# UNO_florist_automata_V1_0.net
KiCad netlist of a schematic drawn in EAGLE
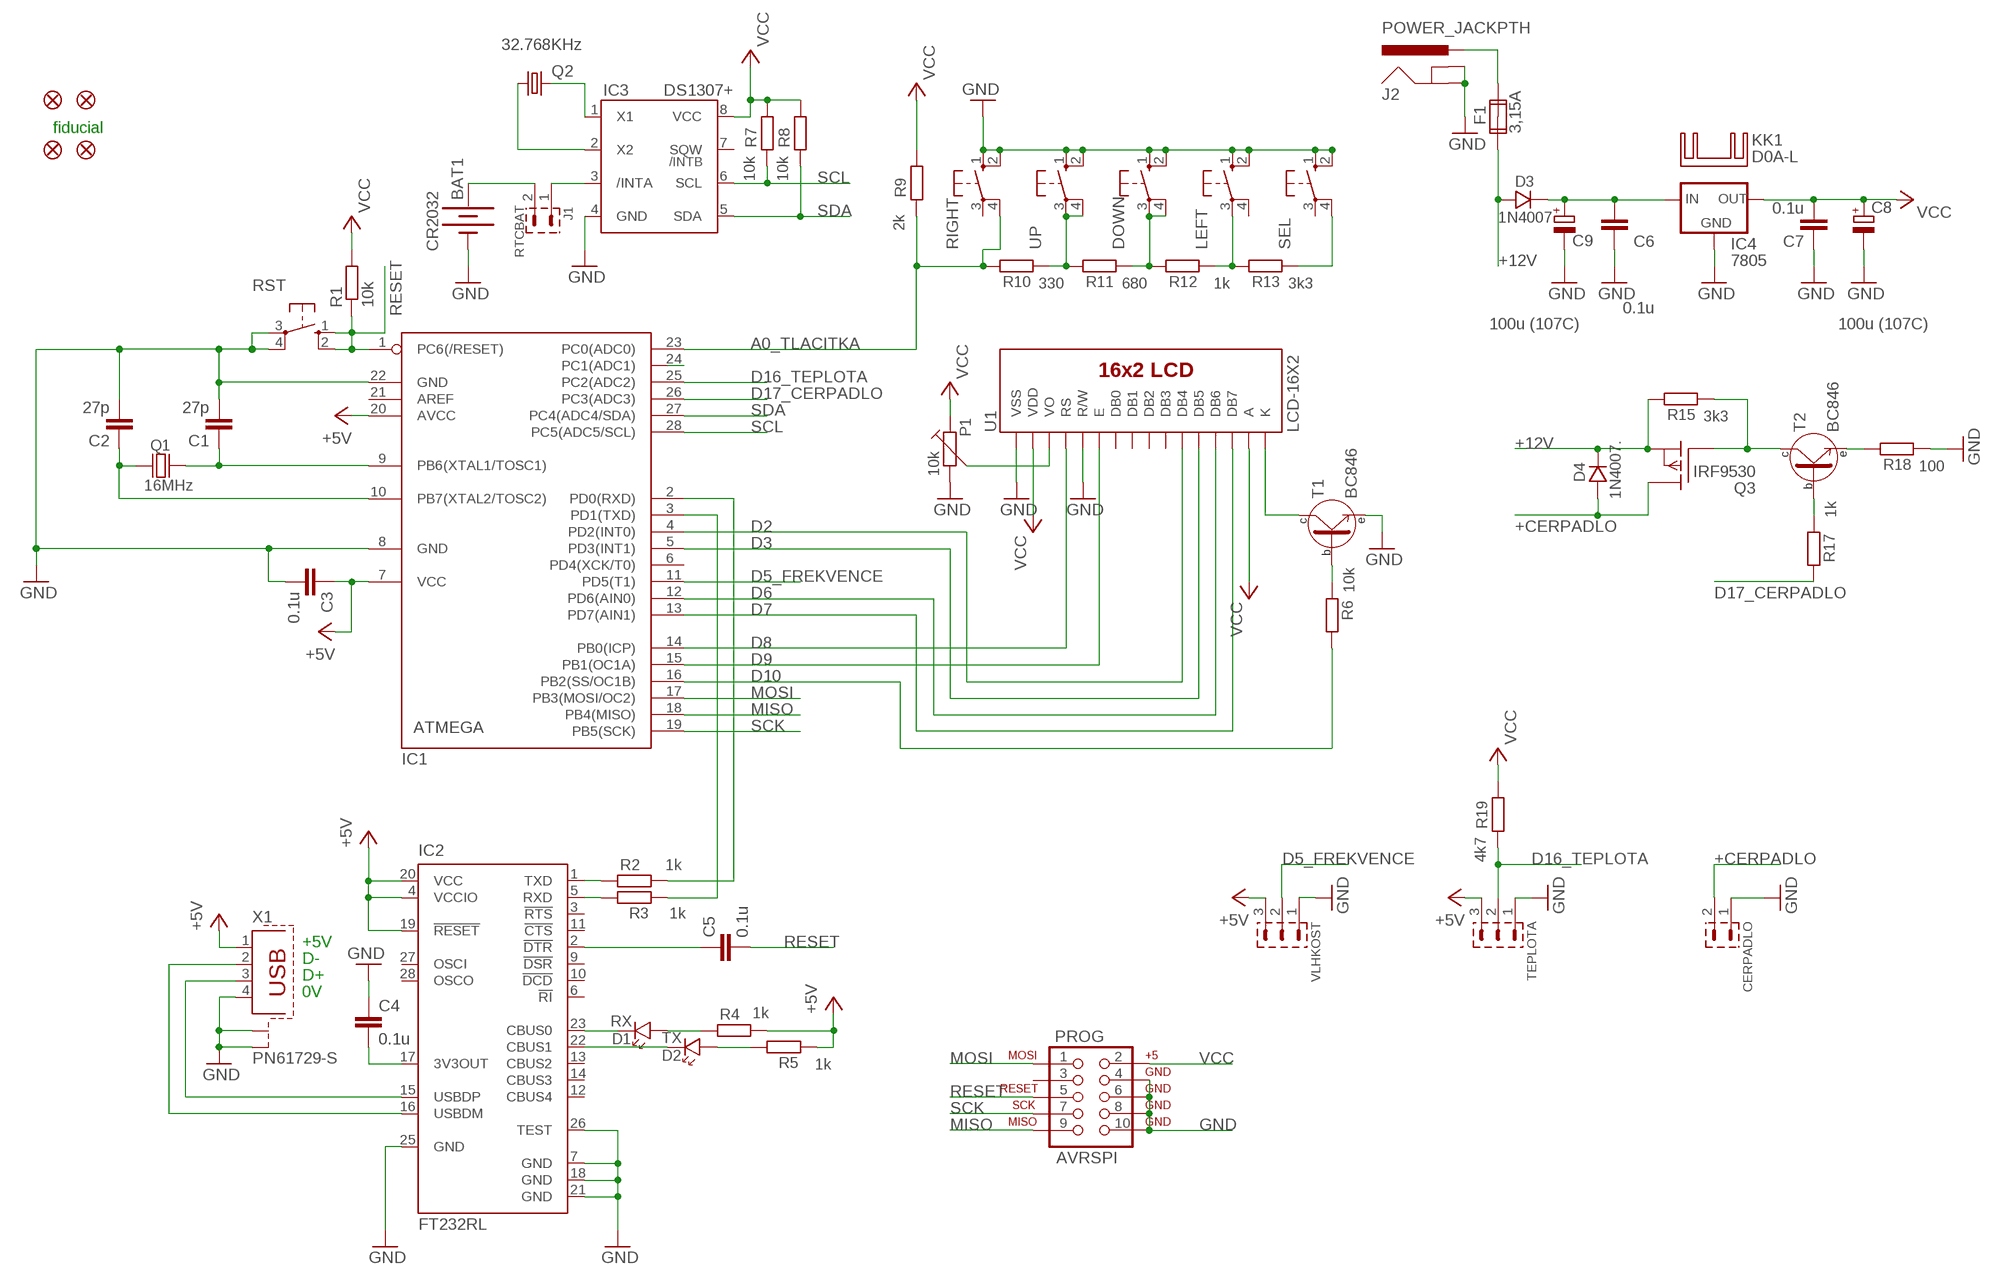
[diagram p0: schematic, sheet 1]

(export (version "E")
  (design (tool "Eeschema 10.0.6"))
  (components
    (comp (ref "BAT1")
      (value "CR2032")
      (footprint "eagle-import:BATTCOM_20MM_PTH")
      (libsource (lib "eagle-import") (part "BATTERY20PTH"))
    )
    (comp (ref "C1")
      (value "27p")
      (footprint "eagle-import:C1206")
      (libsource (lib "eagle-import") (part "C-EUC1206"))
    )
    (comp (ref "C2")
      (value "27p")
      (footprint "eagle-import:C1206")
      (libsource (lib "eagle-import") (part "C-EUC1206"))
    )
    (comp (ref "C3")
      (value "0.1u")
      (footprint "eagle-import:C1206")
      (libsource (lib "eagle-import") (part "C-EUC1206"))
    )
    (comp (ref "C4")
      (value "0.1u")
      (footprint "eagle-import:C1206")
      (libsource (lib "eagle-import") (part "C-EUC1206"))
    )
    (comp (ref "C5")
      (value "0.1u")
      (footprint "eagle-import:C1206")
      (libsource (lib "eagle-import") (part "C-EUC1206"))
    )
    (comp (ref "C6")
      (value "0.1u")
      (footprint "eagle-import:C1206")
      (libsource (lib "eagle-import") (part "C-EUC1206"))
    )
    (comp (ref "C7")
      (value "0.1u")
      (footprint "eagle-import:C1206")
      (libsource (lib "eagle-import") (part "C-EUC1206"))
    )
    (comp (ref "C8")
      (value "100u (107C)")
      (footprint "eagle-import:C_6032-28W")
      (libsource (lib "eagle-import") (part "CPOL-EUC/6032-28W"))
    )
    (comp (ref "C9")
      (value "100u (107C)")
      (footprint "eagle-import:C_6032-28W")
      (libsource (lib "eagle-import") (part "CPOL-EUC/6032-28W"))
    )
    (comp (ref "CERPADLO")
      (value "PSH02-02P")
      (footprint "eagle-import:PSH02-02P")
      (libsource (lib "eagle-import") (part "PSH02-02P"))
    )
    (comp (ref "D1")
      (value "RX")
      (footprint "eagle-import:P1206")
      (libsource (lib "eagle-import") (part "LED_1206"))
    )
    (comp (ref "D2")
      (value "TX")
      (footprint "eagle-import:P1206")
      (libsource (lib "eagle-import") (part "LED_1206"))
    )
    (comp (ref "D3")
      (value "1N4007.")
      (footprint "eagle-import:SM-1")
      (libsource (lib "eagle-import") (part "1N4007."))
    )
    (comp (ref "D4")
      (value "1N4007.")
      (footprint "eagle-import:SM-1")
      (libsource (lib "eagle-import") (part "1N4007."))
    )
    (comp (ref "DOWN")
      (value "10-XX")
      (footprint "eagle-import:B3F-10XX")
      (libsource (lib "eagle-import") (part "10-XX"))
    )
    (comp (ref "F1")
      (value "3,15A")
      (footprint "eagle-import:FUSE1")
      (libsource (lib "eagle-import") (part "FUSE2P"))
    )
    (comp (ref "FID1")
      (value "FIDUCIAL1.5X3")
      (footprint "eagle-import:FIDUCIAL-1.5X3")
      (libsource (lib "eagle-import") (part "FIDUCIAL1.5X3"))
    )
    (comp (ref "FID2")
      (value "FIDUCIAL1.5X3")
      (footprint "eagle-import:FIDUCIAL-1.5X3")
      (libsource (lib "eagle-import") (part "FIDUCIAL1.5X3"))
    )
    (comp (ref "FID3")
      (value "FIDUCIAL1.5X3")
      (footprint "eagle-import:FIDUCIAL-1.5X3")
      (libsource (lib "eagle-import") (part "FIDUCIAL1.5X3"))
    )
    (comp (ref "FID4")
      (value "FIDUCIAL1.5X3")
      (footprint "eagle-import:FIDUCIAL-1.5X3")
      (libsource (lib "eagle-import") (part "FIDUCIAL1.5X3"))
    )
    (comp (ref "IC1")
      (value "ATMEGA")
      (footprint "eagle-import:DIL28-3")
      (libsource (lib "eagle-import") (part "MEGA8-P"))
    )
    (comp (ref "IC2")
      (value "FT232RL")
      (footprint "eagle-import:SSOP28")
      (libsource (lib "eagle-import") (part "FT232RL"))
    )
    (comp (ref "IC3")
      (value "DS1307+")
      (footprint "eagle-import:SO08")
      (libsource (lib "eagle-import") (part "DS1337S+"))
    )
    (comp (ref "IC4")
      (value "7805")
      (footprint "eagle-import:78XXL")
      (libsource (lib "eagle-import") (part "78XXL"))
    )
    (comp (ref "J1")
      (value "RTCBAT")
      (footprint "eagle-import:S1G2_JUM")
      (libsource (lib "eagle-import") (part "S1G2_JUMP"))
    )
    (comp (ref "J2")
      (value "POWER_JACKPTH")
      (footprint "eagle-import:POWER_JACK_PTH")
      (libsource (lib "eagle-import") (part "POWER_JACKPTH"))
    )
    (comp (ref "KK1")
      (value "D0A-L")
      (footprint "eagle-import:D02A-L")
      (libsource (lib "eagle-import") (part "D0A-L"))
    )
    (comp (ref "LEFT")
      (value "10-XX")
      (footprint "eagle-import:B3F-10XX")
      (libsource (lib "eagle-import") (part "10-XX"))
    )
    (comp (ref "P1")
      (value "10k")
      (footprint "eagle-import:PT10V")
      (libsource (lib "eagle-import") (part "TRIMRPT10V"))
    )
    (comp (ref "PROG")
      (value "AVRSPI")
      (footprint "eagle-import:2X5-SHROUDED_LOCK")
      (libsource (lib "eagle-import") (part "AVR_SPI_PROG2LOCK"))
    )
    (comp (ref "Q1")
      (value "16MHz")
      (footprint "eagle-import:HC-49U")
      (libsource (lib "eagle-import") (part "Q_HC-49U"))
    )
    (comp (ref "Q2")
      (value "32.768KHz")
      (footprint "eagle-import:TC38H")
      (libsource (lib "eagle-import") (part "CRYSTALTC38H"))
    )
    (comp (ref "Q3")
      (value "IRF9530")
      (footprint "eagle-import:TO220")
      (libsource (lib "eagle-import") (part "IRF9530"))
    )
    (comp (ref "R1")
      (value "10k")
      (footprint "eagle-import:M1206")
      (libsource (lib "eagle-import") (part "R-EU_M1206"))
    )
    (comp (ref "R2")
      (value "1k")
      (footprint "eagle-import:M1206")
      (libsource (lib "eagle-import") (part "R-EU_M1206"))
    )
    (comp (ref "R3")
      (value "1k")
      (footprint "eagle-import:M1206")
      (libsource (lib "eagle-import") (part "R-EU_M1206"))
    )
    (comp (ref "R4")
      (value "1k")
      (footprint "eagle-import:M1206")
      (libsource (lib "eagle-import") (part "R-EU_M1206"))
    )
    (comp (ref "R5")
      (value "1k")
      (footprint "eagle-import:M1206")
      (libsource (lib "eagle-import") (part "R-EU_M1206"))
    )
    (comp (ref "R6")
      (value "10k")
      (footprint "eagle-import:M1206")
      (libsource (lib "eagle-import") (part "R-EU_M1206"))
    )
    (comp (ref "R7")
      (value "10k")
      (footprint "eagle-import:M1206")
      (libsource (lib "eagle-import") (part "R-EU_M1206"))
    )
    (comp (ref "R8")
      (value "10k")
      (footprint "eagle-import:M1206")
      (libsource (lib "eagle-import") (part "R-EU_M1206"))
    )
    (comp (ref "R9")
      (value "2k")
      (footprint "eagle-import:M1206")
      (libsource (lib "eagle-import") (part "R-EU_M1206"))
    )
    (comp (ref "R10")
      (value "330")
      (footprint "eagle-import:M1206")
      (libsource (lib "eagle-import") (part "R-EU_M1206"))
    )
    (comp (ref "R11")
      (value "680")
      (footprint "eagle-import:M1206")
      (libsource (lib "eagle-import") (part "R-EU_M1206"))
    )
    (comp (ref "R12")
      (value "1k")
      (footprint "eagle-import:M1206")
      (libsource (lib "eagle-import") (part "R-EU_M1206"))
    )
    (comp (ref "R13")
      (value "3k3")
      (footprint "eagle-import:M1206")
      (libsource (lib "eagle-import") (part "R-EU_M1206"))
    )
    (comp (ref "R15")
      (value "3k3")
      (footprint "eagle-import:M1206")
      (libsource (lib "eagle-import") (part "R-EU_M1206"))
    )
    (comp (ref "R17")
      (value "1k")
      (footprint "eagle-import:M1206")
      (libsource (lib "eagle-import") (part "R-EU_M1206"))
    )
    (comp (ref "R18")
      (value "100")
      (footprint "eagle-import:M1206")
      (libsource (lib "eagle-import") (part "R-EU_M1206"))
    )
    (comp (ref "R19")
      (value "4k7")
      (footprint "eagle-import:M1206")
      (libsource (lib "eagle-import") (part "R-EU_M1206"))
    )
    (comp (ref "RIGHT")
      (value "10-XX")
      (footprint "eagle-import:B3F-10XX")
      (libsource (lib "eagle-import") (part "10-XX"))
    )
    (comp (ref "RST")
      (value "10-XX")
      (footprint "eagle-import:B3F-10XX")
      (libsource (lib "eagle-import") (part "10-XX"))
    )
    (comp (ref "SEL")
      (value "10-XX")
      (footprint "eagle-import:B3F-10XX")
      (libsource (lib "eagle-import") (part "10-XX"))
    )
    (comp (ref "T1")
      (value "BC846")
      (footprint "eagle-import:SOT-23")
      (libsource (lib "eagle-import") (part "BC846"))
    )
    (comp (ref "T2")
      (value "BC846")
      (footprint "eagle-import:SOT-23")
      (libsource (lib "eagle-import") (part "BC846"))
    )
    (comp (ref "TEPLOTA")
      (value "PSH02-03P")
      (footprint "eagle-import:PSH02-03P")
      (libsource (lib "eagle-import") (part "PSH02-03P"))
    )
    (comp (ref "U1")
      (value "LCD-16X2")
      (footprint "eagle-import:LCD-16X2_NOSILK")
      (libsource (lib "eagle-import") (part "LCD-16X2NOSILK"))
    )
    (comp (ref "UP")
      (value "10-XX")
      (footprint "eagle-import:B3F-10XX")
      (libsource (lib "eagle-import") (part "10-XX"))
    )
    (comp (ref "VLHKOST")
      (value "PSH02-03P")
      (footprint "eagle-import:PSH02-03P")
      (libsource (lib "eagle-import") (part "PSH02-03P"))
    )
    (comp (ref "X1")
      (value "PN61729-S")
      (footprint "eagle-import:PN61729-S")
      (libsource (lib "eagle-import") (part "PN61729-S"))
    )
  )
  (nets
    (net (code "1") (name "+5V") (class "Default")
      (node (ref "C3") (pin "1") (pinfunction "1_1") (pintype "passive"))
      (node (ref "C7") (pin "2") (pinfunction "2_2") (pintype "passive"))
      (node (ref "C8") (pin "+") (pinfunction "+_+") (pintype "passive"))
      (node (ref "IC1") (pin "20") (pinfunction "AVCC_20") (pintype "power_in"))
      (node (ref "IC1") (pin "7") (pinfunction "VCC_7") (pintype "power_in"))
      (node (ref "IC2") (pin "19") (pinfunction "~{RESET}_19") (pintype "input"))
      (node (ref "IC2") (pin "20") (pinfunction "VCC_20") (pintype "power_in"))
      (node (ref "IC2") (pin "4") (pinfunction "VCCIO_4") (pintype "power_in"))
      (node (ref "IC3") (pin "8") (pinfunction "VCC_8") (pintype "power_in"))
      (node (ref "IC4") (pin "OUT") (pinfunction "OUT_OUT") (pintype "passive"))
      (node (ref "P1") (pin "1") (pinfunction "1_1") (pintype "passive"))
      (node (ref "PROG") (pin "2") (pinfunction "2_2") (pintype "passive"))
      (node (ref "R1") (pin "2") (pinfunction "2_2") (pintype "passive"))
      (node (ref "R19") (pin "2") (pinfunction "2_2") (pintype "passive"))
      (node (ref "R4") (pin "2") (pinfunction "2_2") (pintype "passive"))
      (node (ref "R5") (pin "1") (pinfunction "1_1") (pintype "passive"))
      (node (ref "R7") (pin "2") (pinfunction "2_2") (pintype "passive"))
      (node (ref "R8") (pin "2") (pinfunction "2_2") (pintype "passive"))
      (node (ref "R9") (pin "2") (pinfunction "2_2") (pintype "passive"))
      (node (ref "TEPLOTA") (pin "3") (pinfunction "3_3") (pintype "passive"))
      (node (ref "U1") (pin "15") (pinfunction "A_15") (pintype "power_in"))
      (node (ref "U1") (pin "2") (pinfunction "VDD_2") (pintype "power_in"))
      (node (ref "VLHKOST") (pin "3") (pinfunction "3_3") (pintype "passive"))
      (node (ref "X1") (pin "1") (pinfunction "1_1") (pintype "passive"))
    )
    (net (code "2") (name "/+12V") (class "Default")
      (node (ref "D3") (pin "A") (pinfunction "A_A") (pintype "passive"))
      (node (ref "D4") (pin "K") (pinfunction "K_K") (pintype "passive"))
      (node (ref "F1") (pin "1A") (pinfunction "1A_1A") (pintype "passive"))
      (node (ref "Q3") (pin "3") (pinfunction "S_3") (pintype "passive"))
      (node (ref "R15") (pin "2") (pinfunction "2_2") (pintype "passive"))
    )
    (net (code "3") (name "/+CERPADLO") (class "Default")
      (node (ref "CERPADLO") (pin "2") (pinfunction "2_2") (pintype "passive"))
      (node (ref "D4") (pin "A") (pinfunction "A_A") (pintype "passive"))
      (node (ref "Q3") (pin "2") (pinfunction "D_2") (pintype "passive"))
    )
    (net (code "4") (name "/A0_TLACITKA") (class "Default")
      (node (ref "IC1") (pin "23") (pinfunction "PC0(ADC0)_23") (pintype "bidirectional"))
      (node (ref "R10") (pin "2") (pinfunction "2_2") (pintype "passive"))
      (node (ref "R9") (pin "1") (pinfunction "1_1") (pintype "passive"))
      (node (ref "RIGHT") (pin "4") (pinfunction "P1_4") (pintype "passive"))
    )
    (net (code "5") (name "/D2") (class "Default")
      (node (ref "IC1") (pin "4") (pinfunction "PD2(INT0)_4") (pintype "bidirectional"))
      (node (ref "U1") (pin "11") (pinfunction "DB4_11") (pintype "bidirectional"))
    )
    (net (code "6") (name "/D3") (class "Default")
      (node (ref "IC1") (pin "5") (pinfunction "PD3(INT1)_5") (pintype "bidirectional"))
      (node (ref "U1") (pin "12") (pinfunction "DB5_12") (pintype "bidirectional"))
    )
    (net (code "7") (name "/D5_FREKVENCE") (class "Default")
      (node (ref "IC1") (pin "11") (pinfunction "PD5(T1)_11") (pintype "bidirectional"))
      (node (ref "VLHKOST") (pin "2") (pinfunction "2_2") (pintype "passive"))
    )
    (net (code "8") (name "/D6") (class "Default")
      (node (ref "IC1") (pin "12") (pinfunction "PD6(AIN0)_12") (pintype "bidirectional"))
      (node (ref "U1") (pin "13") (pinfunction "DB6_13") (pintype "bidirectional"))
    )
    (net (code "9") (name "/D7") (class "Default")
      (node (ref "IC1") (pin "13") (pinfunction "PD7(AIN1)_13") (pintype "bidirectional"))
      (node (ref "U1") (pin "14") (pinfunction "DB7_14") (pintype "bidirectional"))
    )
    (net (code "10") (name "/D8") (class "Default")
      (node (ref "IC1") (pin "14") (pinfunction "PB0(ICP)_14") (pintype "bidirectional"))
      (node (ref "U1") (pin "4") (pinfunction "RS_4") (pintype "input"))
    )
    (net (code "11") (name "/D9") (class "Default")
      (node (ref "IC1") (pin "15") (pinfunction "PB1(OC1A)_15") (pintype "bidirectional"))
      (node (ref "U1") (pin "6") (pinfunction "E_6") (pintype "input"))
    )
    (net (code "12") (name "/D10") (class "Default")
      (node (ref "IC1") (pin "16") (pinfunction "PB2(SS/OC1B)_16") (pintype "bidirectional"))
      (node (ref "R6") (pin "2") (pinfunction "2_2") (pintype "passive"))
    )
    (net (code "13") (name "/D16_TEPLOTA") (class "Default")
      (node (ref "IC1") (pin "25") (pinfunction "PC2(ADC2)_25") (pintype "bidirectional"))
      (node (ref "R19") (pin "1") (pinfunction "1_1") (pintype "passive"))
      (node (ref "TEPLOTA") (pin "2") (pinfunction "2_2") (pintype "passive"))
    )
    (net (code "14") (name "/D17_CERPADLO") (class "Default")
      (node (ref "IC1") (pin "26") (pinfunction "PC3(ADC3)_26") (pintype "bidirectional"))
      (node (ref "R17") (pin "2") (pinfunction "2_2") (pintype "passive"))
    )
    (net (code "15") (name "/MISO") (class "Default")
      (node (ref "IC1") (pin "18") (pinfunction "PB4(MISO)_18") (pintype "bidirectional"))
      (node (ref "PROG") (pin "9") (pinfunction "9_9") (pintype "passive"))
    )
    (net (code "16") (name "/MOSI") (class "Default")
      (node (ref "IC1") (pin "17") (pinfunction "PB3(MOSI/OC2)_17") (pintype "bidirectional"))
      (node (ref "PROG") (pin "1") (pinfunction "1_1") (pintype "passive"))
    )
    (net (code "17") (name "/RESET") (class "Default")
      (node (ref "C5") (pin "2") (pinfunction "2_2") (pintype "passive"))
      (node (ref "IC1") (pin "1") (pinfunction "PC6(/RESET)_1") (pintype "bidirectional"))
      (node (ref "PROG") (pin "5") (pinfunction "5_5") (pintype "passive"))
      (node (ref "R1") (pin "1") (pinfunction "1_1") (pintype "passive"))
      (node (ref "RST") (pin "1") (pinfunction "S_1") (pintype "passive"))
      (node (ref "RST") (pin "2") (pinfunction "S1_2") (pintype "passive"))
    )
    (net (code "18") (name "/SCK") (class "Default")
      (node (ref "IC1") (pin "19") (pinfunction "PB5(SCK)_19") (pintype "bidirectional"))
      (node (ref "PROG") (pin "7") (pinfunction "7_7") (pintype "passive"))
    )
    (net (code "19") (name "/SCL") (class "Default")
      (node (ref "IC1") (pin "28") (pinfunction "PC5(ADC5/SCL)_28") (pintype "bidirectional"))
      (node (ref "IC3") (pin "6") (pinfunction "SCL_6") (pintype "bidirectional"))
      (node (ref "R7") (pin "1") (pinfunction "1_1") (pintype "passive"))
    )
    (net (code "20") (name "/SDA") (class "Default")
      (node (ref "IC1") (pin "27") (pinfunction "PC4(ADC4/SDA)_27") (pintype "bidirectional"))
      (node (ref "IC3") (pin "5") (pinfunction "SDA_5") (pintype "bidirectional"))
      (node (ref "R8") (pin "1") (pinfunction "1_1") (pintype "passive"))
    )
    (net (code "21") (name "GND") (class "Default")
      (node (ref "BAT1") (pin "2") (pinfunction "-_2") (pintype "power_in"))
      (node (ref "C1") (pin "2") (pinfunction "2_2") (pintype "passive"))
      (node (ref "C2") (pin "2") (pinfunction "2_2") (pintype "passive"))
      (node (ref "C3") (pin "2") (pinfunction "2_2") (pintype "passive"))
      (node (ref "C4") (pin "1") (pinfunction "1_1") (pintype "passive"))
      (node (ref "C6") (pin "1") (pinfunction "1_1") (pintype "passive"))
      (node (ref "C7") (pin "1") (pinfunction "1_1") (pintype "passive"))
      (node (ref "C8") (pin "-") (pinfunction "-_-") (pintype "passive"))
      (node (ref "C9") (pin "-") (pinfunction "-_-") (pintype "passive"))
      (node (ref "CERPADLO") (pin "1") (pinfunction "1_1") (pintype "passive"))
      (node (ref "DOWN") (pin "1") (pinfunction "S_1") (pintype "passive"))
      (node (ref "DOWN") (pin "2") (pinfunction "S1_2") (pintype "passive"))
      (node (ref "IC1") (pin "22") (pinfunction "GND_22") (pintype "power_in"))
      (node (ref "IC1") (pin "8") (pinfunction "GND_8") (pintype "power_in"))
      (node (ref "IC2") (pin "18") (pinfunction "GND_18") (pintype "power_in"))
      (node (ref "IC2") (pin "21") (pinfunction "GND_21") (pintype "power_in"))
      (node (ref "IC2") (pin "25") (pinfunction "GND_25") (pintype "power_in"))
      (node (ref "IC2") (pin "26") (pinfunction "TEST_26") (pintype "input"))
      (node (ref "IC2") (pin "7") (pinfunction "GND_7") (pintype "power_in"))
      (node (ref "IC3") (pin "4") (pinfunction "GND_4") (pintype "power_in"))
      (node (ref "IC4") (pin "GND") (pinfunction "GND_GND") (pintype "input"))
      (node (ref "J2") (pin "GND") (pinfunction "GND_GND") (pintype "bidirectional"))
      (node (ref "J2") (pin "GNDBREAK") (pinfunction "GNDBREAK_GNDBREAK") (pintype "bidirectional"))
      (node (ref "LEFT") (pin "1") (pinfunction "S_1") (pintype "passive"))
      (node (ref "LEFT") (pin "2") (pinfunction "S1_2") (pintype "passive"))
      (node (ref "P1") (pin "2") (pinfunction "2_2") (pintype "passive"))
      (node (ref "PROG") (pin "10") (pinfunction "10_10") (pintype "passive"))
      (node (ref "PROG") (pin "4") (pinfunction "4_4") (pintype "passive"))
      (node (ref "PROG") (pin "6") (pinfunction "6_6") (pintype "passive"))
      (node (ref "PROG") (pin "8") (pinfunction "8_8") (pintype "passive"))
      (node (ref "R18") (pin "1") (pinfunction "1_1") (pintype "passive"))
      (node (ref "RIGHT") (pin "1") (pinfunction "S_1") (pintype "passive"))
      (node (ref "RIGHT") (pin "2") (pinfunction "S1_2") (pintype "passive"))
      (node (ref "RST") (pin "3") (pinfunction "P_3") (pintype "passive"))
      (node (ref "RST") (pin "4") (pinfunction "P1_4") (pintype "passive"))
      (node (ref "SEL") (pin "1") (pinfunction "S_1") (pintype "passive"))
      (node (ref "SEL") (pin "2") (pinfunction "S1_2") (pintype "passive"))
      (node (ref "T1") (pin "2") (pinfunction "E_2") (pintype "passive"))
      (node (ref "TEPLOTA") (pin "1") (pinfunction "1_1") (pintype "passive"))
      (node (ref "U1") (pin "1") (pinfunction "VSS_1") (pintype "power_in"))
      (node (ref "U1") (pin "5") (pinfunction "R/W_5") (pintype "input"))
      (node (ref "UP") (pin "1") (pinfunction "S_1") (pintype "passive"))
      (node (ref "UP") (pin "2") (pinfunction "S1_2") (pintype "passive"))
      (node (ref "VLHKOST") (pin "1") (pinfunction "1_1") (pintype "passive"))
      (node (ref "X1") (pin "4") (pinfunction "4_4") (pintype "passive"))
      (node (ref "X1") (pin "S1") (pinfunction "S1_S1") (pintype "passive"))
      (node (ref "X1") (pin "S2") (pinfunction "S2_S2") (pintype "passive"))
    )
    (net (code "22") (name "Net-(BAT1-+)") (class "Default")
      (node (ref "BAT1") (pin "1") (pinfunction "+_1") (pintype "power_in"))
      (node (ref "J1") (pin "2") (pinfunction "2_2") (pintype "passive"))
    )
    (net (code "23") (name "Net-(C6-Pad2)") (class "Default")
      (node (ref "C6") (pin "2") (pinfunction "2_2") (pintype "passive"))
      (node (ref "C9") (pin "+") (pinfunction "+_+") (pintype "passive"))
      (node (ref "D3") (pin "K") (pinfunction "K_K") (pintype "passive"))
      (node (ref "IC4") (pin "IN") (pinfunction "IN_IN") (pintype "input"))
    )
    (net (code "24") (name "Net-(D1-PadA)") (class "Default")
      (node (ref "D1") (pin "A") (pinfunction "A_A") (pintype "passive"))
      (node (ref "R4") (pin "1") (pinfunction "1_1") (pintype "passive"))
    )
    (net (code "25") (name "Net-(D2-PadA)") (class "Default")
      (node (ref "D2") (pin "A") (pinfunction "A_A") (pintype "passive"))
      (node (ref "R5") (pin "2") (pinfunction "2_2") (pintype "passive"))
    )
    (net (code "26") (name "Net-(DOWN-P)") (class "Default")
      (node (ref "DOWN") (pin "3") (pinfunction "P_3") (pintype "passive"))
      (node (ref "DOWN") (pin "4") (pinfunction "P1_4") (pintype "passive"))
      (node (ref "R11") (pin "1") (pinfunction "1_1") (pintype "passive"))
      (node (ref "R12") (pin "2") (pinfunction "2_2") (pintype "passive"))
    )
    (net (code "27") (name "Net-(F1-Pad2A)") (class "Default")
      (node (ref "F1") (pin "2A") (pinfunction "2A_2A") (pintype "passive"))
      (node (ref "J2") (pin "PWR") (pinfunction "PWR_PWR") (pintype "bidirectional"))
    )
    (net (code "28") (name "Net-(IC1-PB6(XTAL1{slash}TOSC1))") (class "Default")
      (node (ref "C1") (pin "1") (pinfunction "1_1") (pintype "passive"))
      (node (ref "IC1") (pin "9") (pinfunction "PB6(XTAL1/TOSC1)_9") (pintype "bidirectional"))
      (node (ref "Q1") (pin "2") (pinfunction "2_2") (pintype "passive"))
    )
    (net (code "29") (name "Net-(IC1-PB7(XTAL2{slash}TOSC2))") (class "Default")
      (node (ref "C2") (pin "1") (pinfunction "1_1") (pintype "passive"))
      (node (ref "IC1") (pin "10") (pinfunction "PB7(XTAL2/TOSC2)_10") (pintype "bidirectional"))
      (node (ref "Q1") (pin "1") (pinfunction "1_1") (pintype "passive"))
    )
    (net (code "30") (name "Net-(IC1-PD0(RXD))") (class "Default")
      (node (ref "IC1") (pin "2") (pinfunction "PD0(RXD)_2") (pintype "bidirectional"))
      (node (ref "R2") (pin "2") (pinfunction "2_2") (pintype "passive"))
    )
    (net (code "31") (name "Net-(IC1-PD1(TXD))") (class "Default")
      (node (ref "IC1") (pin "3") (pinfunction "PD1(TXD)_3") (pintype "bidirectional"))
      (node (ref "R3") (pin "1") (pinfunction "1_1") (pintype "passive"))
    )
    (net (code "32") (name "Net-(IC2-3V3OUT)") (class "Default")
      (node (ref "C4") (pin "2") (pinfunction "2_2") (pintype "passive"))
      (node (ref "IC2") (pin "17") (pinfunction "3V3OUT_17") (pintype "output"))
    )
    (net (code "33") (name "Net-(IC2-CBUS0)") (class "Default")
      (node (ref "D1") (pin "K") (pinfunction "K_K") (pintype "passive"))
      (node (ref "IC2") (pin "23") (pinfunction "CBUS0_23") (pintype "bidirectional"))
    )
    (net (code "34") (name "Net-(IC2-CBUS1)") (class "Default")
      (node (ref "D2") (pin "K") (pinfunction "K_K") (pintype "passive"))
      (node (ref "IC2") (pin "22") (pinfunction "CBUS1_22") (pintype "bidirectional"))
    )
    (net (code "35") (name "Net-(IC2-RXD)") (class "Default")
      (node (ref "IC2") (pin "5") (pinfunction "RXD_5") (pintype "input"))
      (node (ref "R3") (pin "2") (pinfunction "2_2") (pintype "passive"))
    )
    (net (code "36") (name "Net-(IC2-TXD)") (class "Default")
      (node (ref "IC2") (pin "1") (pinfunction "TXD_1") (pintype "output"))
      (node (ref "R2") (pin "1") (pinfunction "1_1") (pintype "passive"))
    )
    (net (code "37") (name "Net-(IC2-USBDM)") (class "Default")
      (node (ref "IC2") (pin "16") (pinfunction "USBDM_16") (pintype "bidirectional"))
      (node (ref "X1") (pin "2") (pinfunction "2_2") (pintype "passive"))
    )
    (net (code "38") (name "Net-(IC2-USBDP)") (class "Default")
      (node (ref "IC2") (pin "15") (pinfunction "USBDP_15") (pintype "bidirectional"))
      (node (ref "X1") (pin "3") (pinfunction "3_3") (pintype "passive"))
    )
    (net (code "39") (name "Net-(IC2-~{DTR})") (class "Default")
      (node (ref "C5") (pin "1") (pinfunction "1_1") (pintype "passive"))
      (node (ref "IC2") (pin "2") (pinfunction "~{DTR}_2") (pintype "output"))
    )
    (net (code "40") (name "Net-(IC3-X1)") (class "Default")
      (node (ref "IC3") (pin "1") (pinfunction "X1_1") (pintype "bidirectional"))
      (node (ref "Q2") (pin "2") (pinfunction "2_2") (pintype "passive"))
    )
    (net (code "41") (name "Net-(IC3-X2)") (class "Default")
      (node (ref "IC3") (pin "2") (pinfunction "X2_2") (pintype "bidirectional"))
      (node (ref "Q2") (pin "1") (pinfunction "1_1") (pintype "passive"))
    )
    (net (code "42") (name "Net-(IC3-{slash}INTA)") (class "Default")
      (node (ref "IC3") (pin "3") (pinfunction "/INTA_3") (pintype "bidirectional"))
      (node (ref "J1") (pin "1") (pinfunction "1_1") (pintype "passive"))
    )
    (net (code "43") (name "Net-(LEFT-P)") (class "Default")
      (node (ref "LEFT") (pin "3") (pinfunction "P_3") (pintype "passive"))
      (node (ref "R12") (pin "1") (pinfunction "1_1") (pintype "passive"))
      (node (ref "R13") (pin "2") (pinfunction "2_2") (pintype "passive"))
    )
    (net (code "44") (name "Net-(Q3-G)") (class "Default")
      (node (ref "Q3") (pin "1") (pinfunction "G_1") (pintype "passive"))
      (node (ref "R15") (pin "1") (pinfunction "1_1") (pintype "passive"))
      (node (ref "T2") (pin "3") (pinfunction "C_3") (pintype "passive"))
    )
    (net (code "45") (name "Net-(SEL-P1)") (class "Default")
      (node (ref "R13") (pin "1") (pinfunction "1_1") (pintype "passive"))
      (node (ref "SEL") (pin "4") (pinfunction "P1_4") (pintype "passive"))
    )
    (net (code "46") (name "Net-(T1-B)") (class "Default")
      (node (ref "R6") (pin "1") (pinfunction "1_1") (pintype "passive"))
      (node (ref "T1") (pin "1") (pinfunction "B_1") (pintype "passive"))
    )
    (net (code "47") (name "Net-(T1-C)") (class "Default")
      (node (ref "T1") (pin "3") (pinfunction "C_3") (pintype "passive"))
      (node (ref "U1") (pin "16") (pinfunction "K_16") (pintype "power_in"))
    )
    (net (code "48") (name "Net-(T2-B)") (class "Default")
      (node (ref "R17") (pin "1") (pinfunction "1_1") (pintype "passive"))
      (node (ref "T2") (pin "1") (pinfunction "B_1") (pintype "passive"))
    )
    (net (code "49") (name "Net-(T2-E)") (class "Default")
      (node (ref "R18") (pin "2") (pinfunction "2_2") (pintype "passive"))
      (node (ref "T2") (pin "2") (pinfunction "E_2") (pintype "passive"))
    )
    (net (code "50") (name "Net-(U1-VO)") (class "Default")
      (node (ref "P1") (pin "3") (pinfunction "3_3") (pintype "passive"))
      (node (ref "U1") (pin "3") (pinfunction "VO_3") (pintype "bidirectional"))
    )
    (net (code "51") (name "Net-(UP-P)") (class "Default")
      (node (ref "R10") (pin "1") (pinfunction "1_1") (pintype "passive"))
      (node (ref "R11") (pin "2") (pinfunction "2_2") (pintype "passive"))
      (node (ref "UP") (pin "3") (pinfunction "P_3") (pintype "passive"))
      (node (ref "UP") (pin "4") (pinfunction "P1_4") (pintype "passive"))
    )
    (net (code "52") (name "unconnected-(F1-Pad1B)") (class "Default")
      (node (ref "F1") (pin "1B") (pinfunction "1B_1B") (pintype "passive"))
    )
    (net (code "53") (name "unconnected-(F1-Pad2B)") (class "Default")
      (node (ref "F1") (pin "2B") (pinfunction "2B_2B") (pintype "passive"))
    )
    (net (code "54") (name "unconnected-(IC1-AREF-Pad21)") (class "Default")
      (node (ref "IC1") (pin "21") (pinfunction "AREF_21") (pintype "passive"))
    )
    (net (code "55") (name "unconnected-(IC1-PC1(ADC1)-Pad24)") (class "Default")
      (node (ref "IC1") (pin "24") (pinfunction "PC1(ADC1)_24") (pintype "bidirectional"))
    )
    (net (code "56") (name "unconnected-(IC1-PD4(XCK{slash}T0)-Pad6)") (class "Default")
      (node (ref "IC1") (pin "6") (pinfunction "PD4(XCK/T0)_6") (pintype "bidirectional"))
    )
    (net (code "57") (name "unconnected-(IC2-CBUS2-Pad13)") (class "Default")
      (node (ref "IC2") (pin "13") (pinfunction "CBUS2_13") (pintype "bidirectional"))
    )
    (net (code "58") (name "unconnected-(IC2-CBUS3-Pad14)") (class "Default")
      (node (ref "IC2") (pin "14") (pinfunction "CBUS3_14") (pintype "bidirectional"))
    )
    (net (code "59") (name "unconnected-(IC2-CBUS4-Pad12)") (class "Default")
      (node (ref "IC2") (pin "12") (pinfunction "CBUS4_12") (pintype "bidirectional"))
    )
    (net (code "60") (name "unconnected-(IC2-OSCI-Pad27)") (class "Default")
      (node (ref "IC2") (pin "27") (pinfunction "OSCI_27") (pintype "input"))
    )
    (net (code "61") (name "unconnected-(IC2-OSCO-Pad28)") (class "Default")
      (node (ref "IC2") (pin "28") (pinfunction "OSCO_28") (pintype "output"))
    )
    (net (code "62") (name "unconnected-(IC2-~{CTS}-Pad11)") (class "Default")
      (node (ref "IC2") (pin "11") (pinfunction "~{CTS}_11") (pintype "input"))
    )
    (net (code "63") (name "unconnected-(IC2-~{DCD}-Pad10)") (class "Default")
      (node (ref "IC2") (pin "10") (pinfunction "~{DCD}_10") (pintype "input"))
    )
    (net (code "64") (name "unconnected-(IC2-~{DSR}-Pad9)") (class "Default")
      (node (ref "IC2") (pin "9") (pinfunction "~{DSR}_9") (pintype "input"))
    )
    (net (code "65") (name "unconnected-(IC2-~{RI}-Pad6)") (class "Default")
      (node (ref "IC2") (pin "6") (pinfunction "~{RI}_6") (pintype "input"))
    )
    (net (code "66") (name "unconnected-(IC2-~{RTS}-Pad3)") (class "Default")
      (node (ref "IC2") (pin "3") (pinfunction "~{RTS}_3") (pintype "output"))
    )
    (net (code "67") (name "unconnected-(IC3-SQW-Pad7)") (class "Default")
      (node (ref "IC3") (pin "7") (pinfunction "SQW_7") (pintype "bidirectional"))
    )
    (net (code "68") (name "unconnected-(LEFT-P1-Pad4)") (class "Default")
      (node (ref "LEFT") (pin "4") (pinfunction "P1_4") (pintype "passive"))
    )
    (net (code "69") (name "unconnected-(PROG-Pad3)") (class "Default")
      (node (ref "PROG") (pin "3") (pinfunction "3_3") (pintype "passive"))
    )
    (net (code "70") (name "unconnected-(RIGHT-P-Pad3)") (class "Default")
      (node (ref "RIGHT") (pin "3") (pinfunction "P_3") (pintype "passive"))
    )
    (net (code "71") (name "unconnected-(SEL-P-Pad3)") (class "Default")
      (node (ref "SEL") (pin "3") (pinfunction "P_3") (pintype "passive"))
    )
    (net (code "72") (name "unconnected-(U1-DB0-Pad7)") (class "Default")
      (node (ref "U1") (pin "7") (pinfunction "DB0_7") (pintype "bidirectional"))
    )
    (net (code "73") (name "unconnected-(U1-DB1-Pad8)") (class "Default")
      (node (ref "U1") (pin "8") (pinfunction "DB1_8") (pintype "bidirectional"))
    )
    (net (code "74") (name "unconnected-(U1-DB2-Pad9)") (class "Default")
      (node (ref "U1") (pin "9") (pinfunction "DB2_9") (pintype "bidirectional"))
    )
    (net (code "75") (name "unconnected-(U1-DB3-Pad10)") (class "Default")
      (node (ref "U1") (pin "10") (pinfunction "DB3_10") (pintype "bidirectional"))
    )
  )
)
